# CPU_DIN_mainboard_v2.net
KiCad netlist of a schematic drawn in Altium Designer
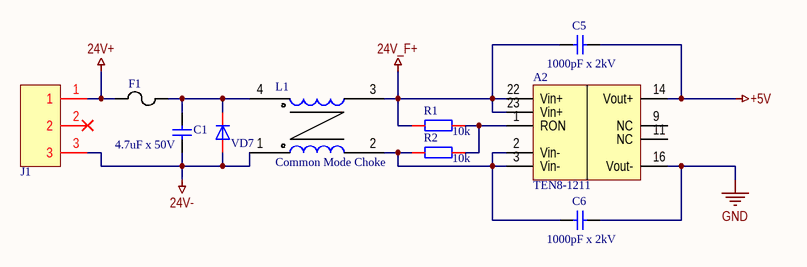
[diagram p0: CPU_DIN_mainboard_v2.SchDoc]

(export (version "E")
  (design (tool "Eeschema 10.0.6"))
  (components
    (comp (ref "A2")
      (value "TEN8-1211")
      (footprint "dcdc_ten8-1211")
      (description "Traco Isolated DC/DC")
      (libsource (lib "Lib_001") (part "TEN8-1211"))
    )
    (comp (ref "C1")
      (value "4.7uF x 50V")
      (footprint "C1206")
      (fields (field (name "PARTNUM") "GRM31CR71H475KA12L"))
      (libsource (lib "Lib_001") (part "CAP_SMD"))
    )
    (comp (ref "C5") (value "1000pF x 2kV") (footprint "c1206") (libsource (lib "Lib_001") (part "CAP_SMD")))
    (comp (ref "C6") (value "1000pF x 2kV") (footprint "c1206") (libsource (lib "Lib_001") (part "CAP_SMD")))
    (comp (ref "F1")
      (value "FUSE")
      (footprint "MF-SM100")
      (fields (field (name "PARTNUM") "MF-SM100-2"))
      (libsource (lib "Lib_001") (part "FUSE"))
    )
    (comp (ref "J1")
      (value "Terminal block TB-3")
      (footprint "TB-3_ser370")
      (libsource (lib "Lib_001") (part "TB-3"))
    )
    (comp (ref "L1")
      (value "Common Mode Choke")
      (footprint "TCK-050")
      (fields (field (name "PARTNUM") "TCK-050"))
      (libsource (lib "Lib_001") (part "L_CHOKE"))
    )
    (comp (ref "R1") (value "10k") (footprint "R0805") (libsource (lib "Lib_001") (part "RES_SMD")))
    (comp (ref "R2") (value "10k") (footprint "R0805") (libsource (lib "Lib_001") (part "RES_SMD")))
    (comp (ref "VD7")
      (value "15MQ040N")
      (footprint "SMA DIOD")
      (fields (field (name "PARTNUM") "VS-15MQ040NTRPBF"))
      (libsource (lib "Lib_001") (part "DIOD"))
    )
  )
  (nets
    (net (code "1") (name "+5V") (class "Default")
      (node (ref "A2") (pin "14") (pinfunction "Vout+_14") (pintype "passive"))
      (node (ref "C5") (pin "2") (pinfunction "2_2") (pintype "passive"))
    )
    (net (code "2") (name "24V+") (class "Default")
      (node (ref "F1") (pin "1") (pinfunction "1_1") (pintype "passive"))
      (node (ref "J1") (pin "1") (pinfunction "1_1") (pintype "passive"))
    )
    (net (code "3") (name "24V-") (class "Default")
      (node (ref "C1") (pin "2") (pinfunction "2_2") (pintype "passive"))
      (node (ref "J1") (pin "3") (pinfunction "3_3") (pintype "passive"))
      (node (ref "L1") (pin "1") (pinfunction "1_1") (pintype "passive"))
      (node (ref "VD7") (pin "A") (pinfunction "A_A") (pintype "passive"))
    )
    (net (code "4") (name "24V_F+") (class "Default")
      (node (ref "A2") (pin "22") (pinfunction "Vin+_22") (pintype "passive"))
      (node (ref "A2") (pin "23") (pinfunction "Vin+_23") (pintype "passive"))
      (node (ref "C5") (pin "1") (pinfunction "1_1") (pintype "passive"))
      (node (ref "L1") (pin "3") (pinfunction "3_3") (pintype "passive"))
      (node (ref "R1") (pin "2") (pinfunction "2_2") (pintype "passive"))
    )
    (net (code "5") (name "GND") (class "Default")
      (node (ref "A2") (pin "16") (pinfunction "Vout-_16") (pintype "passive"))
      (node (ref "C6") (pin "2") (pinfunction "2_2") (pintype "passive"))
    )
    (net (code "6") (name "Net-(A2-RON)") (class "Default")
      (node (ref "A2") (pin "1") (pinfunction "RON_1") (pintype "passive"))
      (node (ref "R1") (pin "1") (pinfunction "1_1") (pintype "passive"))
      (node (ref "R2") (pin "1") (pinfunction "1_1") (pintype "passive"))
    )
    (net (code "7") (name "Net-(A2-Vin--Pad2)") (class "Default")
      (node (ref "A2") (pin "2") (pinfunction "Vin-_2") (pintype "passive"))
      (node (ref "A2") (pin "3") (pinfunction "Vin-_3") (pintype "passive"))
      (node (ref "C6") (pin "1") (pinfunction "1_1") (pintype "passive"))
      (node (ref "L1") (pin "2") (pinfunction "2_2") (pintype "passive"))
      (node (ref "R2") (pin "2") (pinfunction "2_2") (pintype "passive"))
    )
    (net (code "8") (name "Net-(C1-Pad1)") (class "Default")
      (node (ref "C1") (pin "1") (pinfunction "1_1") (pintype "passive"))
      (node (ref "F1") (pin "2") (pinfunction "2_2") (pintype "passive"))
      (node (ref "L1") (pin "4") (pinfunction "4_4") (pintype "passive"))
      (node (ref "VD7") (pin "K") (pinfunction "K_K") (pintype "passive"))
    )
    (net (code "9") (name "unconnected-(A2-NC-Pad9)") (class "Default")
      (node (ref "A2") (pin "9") (pinfunction "NC_9") (pintype "passive"))
    )
    (net (code "10") (name "unconnected-(A2-NC-Pad11)") (class "Default")
      (node (ref "A2") (pin "11") (pinfunction "NC_11") (pintype "passive"))
    )
    (net (code "11") (name "unconnected-(J1-Pad2)") (class "Default")
      (node (ref "J1") (pin "2") (pinfunction "2_2") (pintype "passive+no_connect"))
    )
  )
)
